# carte_ecureuil2026.net
KiCad netlist of a schematic drawn in Altium Designer
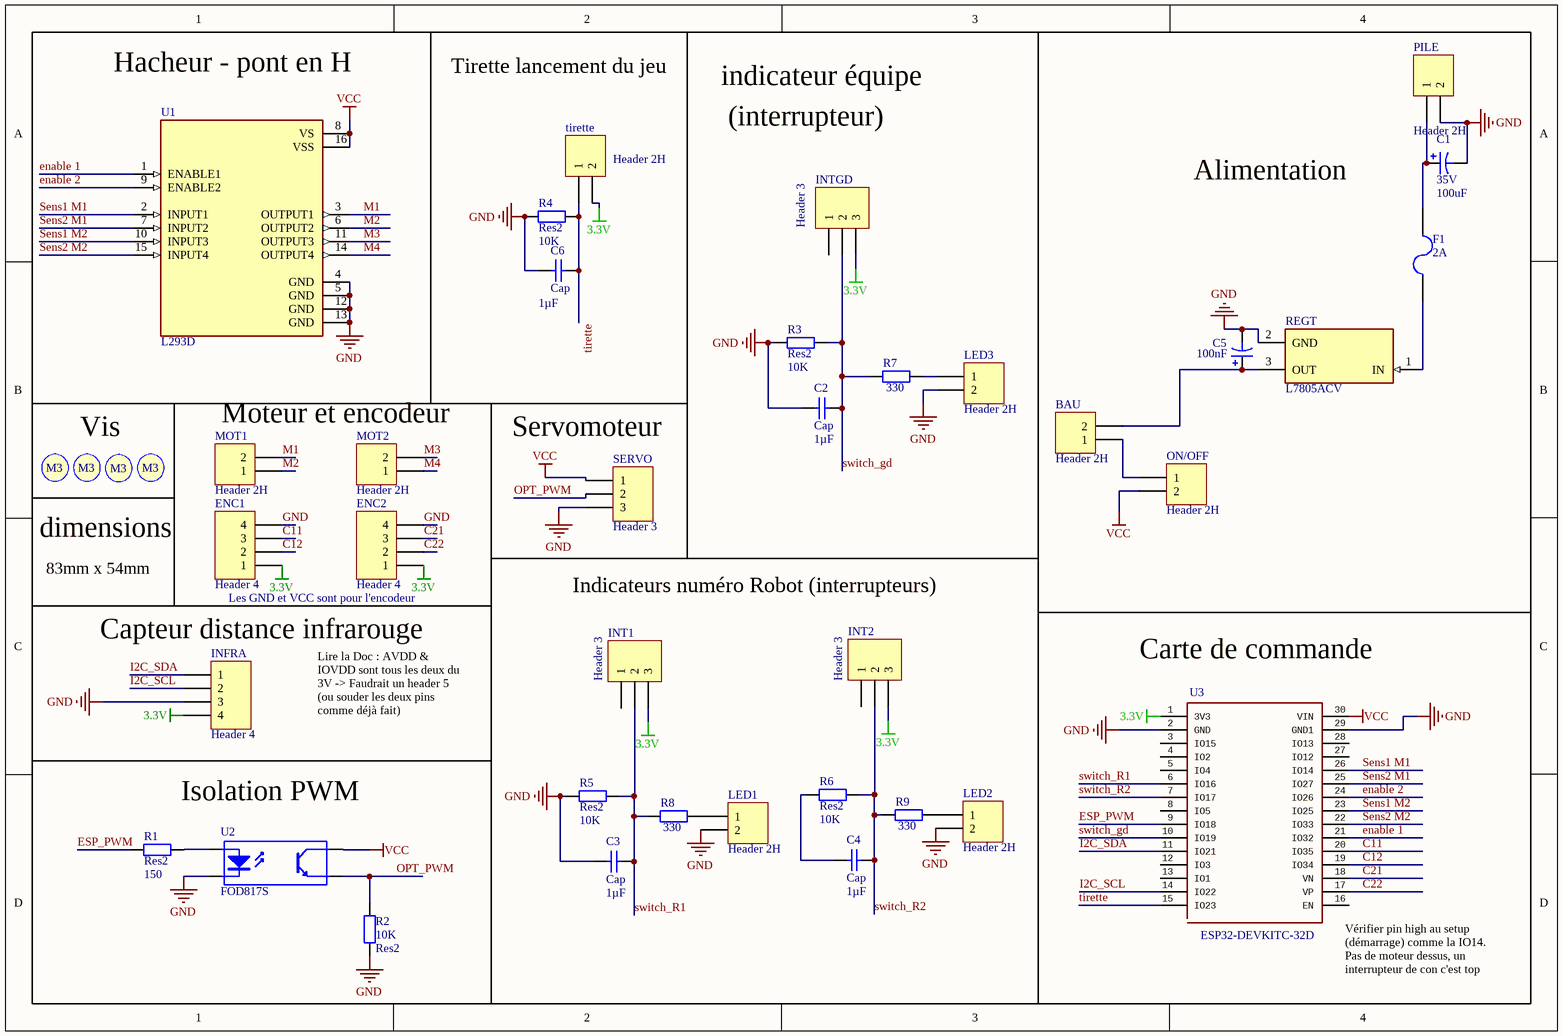
[diagram p0: carte_ecureuil2026.SchDoc]

(export (version "E")
  (design (tool "Eeschema 10.0.6"))
  (components
    (comp (ref "BAU")
      (value "Header 2H")
      (footprint "JST_B2B-XH-A_(LF)(SN)")
      (description "Header, 2-Pin, Right Angle")
      (fields (field (name "PUBLISHER") "Altium Limited"))
      (libsource (lib "") (part "Header 2H_2"))
    )
    (comp (ref "C1")
      (value "35V")
      (footprint "Condensateur")
      (description "Polarized Capacitor (Radial)")
      (fields (field (name "ALTIUM_VALUE") "100uF") (field (name "PUBLISHER") "Altium Limited"))
      (libsource (lib "Miscellaneous Devices") (part "Cap Pol1"))
    )
    (comp (ref "C2")
      (value "Cap")
      (footprint "Capacitor 1206")
      (description "Capacitor")
      (fields (field (name "ALTIUM_VALUE") "1µF") (field (name "PUBLISHER") "Altium Limited"))
      (libsource (lib "Miscellaneous Devices") (part "Cap"))
    )
    (comp (ref "C3")
      (value "Cap")
      (footprint "Capacitor 1206")
      (description "Capacitor")
      (fields (field (name "ALTIUM_VALUE") "1µF") (field (name "PUBLISHER") "Altium Limited"))
      (libsource (lib "Miscellaneous Devices") (part "Cap"))
    )
    (comp (ref "C4")
      (value "Cap")
      (footprint "Capacitor 1206")
      (description "Capacitor")
      (fields (field (name "ALTIUM_VALUE") "1µF") (field (name "PUBLISHER") "Altium Limited"))
      (libsource (lib "Miscellaneous Devices") (part "Cap"))
    )
    (comp (ref "C5")
      (value "100nF")
      (footprint "Condensateur")
      (description "Polarized Capacitor (Radial)")
      (fields (field (name "Comment") "35V") (field (name "PUBLISHER") "Altium Limited"))
      (libsource (lib "Miscellaneous Devices") (part "Cap Pol1"))
    )
    (comp (ref "C6")
      (value "Cap")
      (footprint "Capacitor 1206")
      (description "Capacitor")
      (fields (field (name "ALTIUM_VALUE") "1µF") (field (name "PUBLISHER") "Altium Limited"))
      (libsource (lib "Miscellaneous Devices") (part "Cap"))
    )
    (comp (ref "ENC1")
      (value "Header 4")
      (footprint "B4BXHALFSN")
      (description "Header, 4-Pin")
      (fields (field (name "PUBLISHER") "Altium Limited"))
      (libsource (lib "Miscellaneous Connectors") (part "Header 4"))
    )
    (comp (ref "ENC2")
      (value "Header 4")
      (footprint "B4BXHALFSN")
      (description "Header, 4-Pin")
      (fields (field (name "PUBLISHER") "Altium Limited"))
      (libsource (lib "Miscellaneous Connectors") (part "Header 4"))
    )
    (comp (ref "F1")
      (value "2A")
      (footprint "3.5X2.8X1.9")
      (description "Resettable Fuse αA / JF")
      (fields (field (name "PUBLISHER") "Altium Limited"))
      (libsource (lib "Miscellaneous Devices") (part "Fuse 2"))
    )
    (comp (ref "INFRA")
      (value "Header 4")
      (footprint "B4BXHALFSN")
      (description "Header, 4-Pin")
      (fields (field (name "PUBLISHER") "Altium Limited"))
      (libsource (lib "") (part "Header 4_1"))
    )
    (comp (ref "INT1")
      (value "Header 3")
      (footprint "JST_B3B-XH-A(LF)(SN)")
      (description "Header, 3-Pin")
      (fields (field (name "PUBLISHER") "Altium Limited"))
      (libsource (lib "Miscellaneous Connectors") (part "Header 3"))
    )
    (comp (ref "INT2")
      (value "Header 3")
      (footprint "JST_B3B-XH-A(LF)(SN)")
      (description "Header, 3-Pin")
      (fields (field (name "PUBLISHER") "Altium Limited"))
      (libsource (lib "Miscellaneous Connectors") (part "Header 3"))
    )
    (comp (ref "INTGD")
      (value "Header 3")
      (footprint "JST_B3B-XH-A(LF)(SN)")
      (description "Header, 3-Pin")
      (fields (field (name "PUBLISHER") "Altium Limited"))
      (libsource (lib "Miscellaneous Connectors") (part "Header 3"))
    )
    (comp (ref "LED1")
      (value "Header 2H")
      (footprint "JST_B2B-XH-A_(LF)(SN)")
      (description "Header, 2-Pin, Right Angle")
      (fields (field (name "PUBLISHER") "Altium Limited"))
      (libsource (lib "Miscellaneous Connectors") (part "Header 2H"))
    )
    (comp (ref "LED2")
      (value "Header 2H")
      (footprint "JST_B2B-XH-A_(LF)(SN)")
      (description "Header, 2-Pin, Right Angle")
      (fields (field (name "PUBLISHER") "Altium Limited"))
      (libsource (lib "Miscellaneous Connectors") (part "Header 2H"))
    )
    (comp (ref "LED3")
      (value "Header 2H")
      (footprint "JST_B2B-XH-A_(LF)(SN)")
      (description "Header, 2-Pin, Right Angle")
      (fields (field (name "PUBLISHER") "Altium Limited"))
      (libsource (lib "Miscellaneous Connectors") (part "Header 2H"))
    )
    (comp (ref "MOT1")
      (value "Header 2H")
      (footprint "JST_B2B-XH-A_(LF)(SN)")
      (description "Header, 2-Pin, Right Angle")
      (fields (field (name "PUBLISHER") "Altium Limited"))
      (libsource (lib "") (part "Header 2H_2"))
    )
    (comp (ref "MOT2")
      (value "Header 2H")
      (footprint "JST_B2B-XH-A_(LF)(SN)")
      (description "Header, 2-Pin, Right Angle")
      (fields (field (name "PUBLISHER") "Altium Limited"))
      (libsource (lib "") (part "Header 2H_2"))
    )
    (comp (ref "ON/OFF")
      (value "Header 2H")
      (footprint "JST_B2B-XH-A_(LF)(SN)")
      (description "Header, 2-Pin, Right Angle")
      (fields (field (name "PUBLISHER") "Altium Limited"))
      (libsource (lib "Miscellaneous Connectors") (part "Header 2H"))
    )
    (comp (ref "PILE")
      (value "Header 2H")
      (footprint "JST_B2B-XH-A_(LF)(SN)")
      (description "Header, 2-Pin, Right Angle")
      (fields (field (name "PUBLISHER") "Altium Limited"))
      (libsource (lib "") (part "Header 2H_1"))
    )
    (comp (ref "R1")
      (value "Res2")
      (footprint "Resistor 1206")
      (description "Resistor")
      (fields (field (name "ALTIUM_VALUE") "150") (field (name "PUBLISHER") "Altium Limited"))
      (libsource (lib "Miscellaneous Devices") (part "Res2"))
    )
    (comp (ref "R2")
      (value "Res2")
      (footprint "Resistor 1206")
      (description "Resistor")
      (fields (field (name "ALTIUM_VALUE") "10K") (field (name "PUBLISHER") "Altium Limited"))
      (libsource (lib "") (part "Res2_1"))
    )
    (comp (ref "R3")
      (value "Res2")
      (footprint "Resistor 1206")
      (description "Resistor")
      (fields (field (name "ALTIUM_VALUE") "10K") (field (name "PUBLISHER") "Altium Limited"))
      (libsource (lib "Miscellaneous Devices") (part "Res2"))
    )
    (comp (ref "R4")
      (value "Res2")
      (footprint "Resistor 1206")
      (description "Resistor")
      (fields (field (name "ALTIUM_VALUE") "10K") (field (name "PUBLISHER") "Altium Limited"))
      (libsource (lib "Miscellaneous Devices") (part "Res2"))
    )
    (comp (ref "R5")
      (value "Res2")
      (footprint "Resistor 1206")
      (description "Resistor")
      (fields (field (name "ALTIUM_VALUE") "10K") (field (name "PUBLISHER") "Altium Limited"))
      (libsource (lib "Miscellaneous Devices") (part "Res2"))
    )
    (comp (ref "R6")
      (value "Res2")
      (footprint "Resistor 1206")
      (description "Resistor")
      (fields (field (name "ALTIUM_VALUE") "10K") (field (name "PUBLISHER") "Altium Limited"))
      (libsource (lib "Miscellaneous Devices") (part "Res2"))
    )
    (comp (ref "R7")
      (value "330")
      (footprint "Resistor 1206")
      (description "Resistor")
      (fields (field (name "Comment") "Res2") (field (name "PUBLISHER") "Altium Limited"))
      (libsource (lib "Miscellaneous Devices") (part "Res2"))
    )
    (comp (ref "R8")
      (value "330")
      (footprint "Resistor 1206")
      (description "Resistor")
      (fields (field (name "Comment") "Res2") (field (name "PUBLISHER") "Altium Limited"))
      (libsource (lib "Miscellaneous Devices") (part "Res2"))
    )
    (comp (ref "R9")
      (value "330")
      (footprint "Resistor 1206")
      (description "Resistor")
      (fields (field (name "Comment") "Res2") (field (name "PUBLISHER") "Altium Limited"))
      (libsource (lib "Miscellaneous Devices") (part "Res2"))
    )
    (comp (ref "REGT")
      (value "L7805ACV")
      (footprint "TO254P460X1020X1945-3P")
      (description "Linear Voltage Regulator IC Positive Fixed 1 Output 1.5A TO-220")
      (fields (field (name "MF") "STMicroelectronics"))
      (libsource (lib "L7805ACV") (part "L7805ACV"))
    )
    (comp (ref "S1")
      (value "Screw M3")
      (footprint "Screw M3")
      (libsource (lib "Robot_2019") (part "Screw M3"))
    )
    (comp (ref "S2")
      (value "Screw M3")
      (footprint "Screw M3")
      (libsource (lib "Robot_2019") (part "Screw M3"))
    )
    (comp (ref "S3")
      (value "Screw M3")
      (footprint "Screw M3")
      (libsource (lib "Robot_2019") (part "Screw M3"))
    )
    (comp (ref "S4")
      (value "Screw M3")
      (footprint "Screw M3")
      (libsource (lib "Robot_2019") (part "Screw M3"))
    )
    (comp (ref "SERVO")
      (value "Header 3")
      (footprint "JST_B3B-XH-A(LF)(SN)")
      (description "Header, 3-Pin")
      (fields (field (name "PUBLISHER") "Altium Limited"))
      (libsource (lib "") (part "Header 3_1"))
    )
    (comp (ref "tirette")
      (value "Header 2H")
      (footprint "JST_B2B-XH-A_(LF)(SN)")
      (description "Header, 2-Pin, Right Angle")
      (fields (field (name "PUBLISHER") "Altium Limited"))
      (libsource (lib "") (part "Header 2H_1"))
    )
    (comp (ref "U1")
      (value "L293D")
      (footprint "DIP880W50P254L2000H510Q16")
      (description "Bipolar Motor Driver - Parallel 16-PowerDIP")
      (fields (field (name "MF") "STMicroelectronics"))
      (libsource (lib "L293D") (part "L293D"))
    )
    (comp (ref "U2")
      (value "FOD817S")
      (footprint "SOP254P1016X385-4N")
      (description "4-Pin Phototransistor Optocoupler")
      (fields (field (name "PUBLISHER") "Altium Limited"))
      (libsource (lib "Miscellaneous Devices") (part "Optoisolator1"))
    )
    (comp (ref "U3")
      (value "ESP32-DEVKITC-32D")
      (footprint "MODULE_ESP32-DEVKITV1")
      (description "Eval Board For Esp-Wroom-32")
      (fields (field (name "MF") "Espressif Systems"))
      (libsource (lib "AltiumLibraryDDT") (part "ESP32-DEVKITC-32D"))
    )
  )
  (nets
    (net (code "1") (name "/C11") (class "Default")
      (node (ref "ENC1") (pin "3") (pinfunction "3_3") (pintype "passive"))
      (node (ref "U3") (pin "20") (pinfunction "IO35_20") (pintype "passive"))
    )
    (net (code "2") (name "/C12") (class "Default")
      (node (ref "ENC1") (pin "2") (pinfunction "2_2") (pintype "passive"))
      (node (ref "U3") (pin "19") (pinfunction "IO34_19") (pintype "passive"))
    )
    (net (code "3") (name "/C21") (class "Default")
      (node (ref "ENC2") (pin "3") (pinfunction "3_3") (pintype "passive"))
      (node (ref "U3") (pin "18") (pinfunction "VN_18") (pintype "passive"))
    )
    (net (code "4") (name "/C22") (class "Default")
      (node (ref "ENC2") (pin "2") (pinfunction "2_2") (pintype "passive"))
      (node (ref "U3") (pin "17") (pinfunction "VP_17") (pintype "passive"))
    )
    (net (code "5") (name "/ESP_PWM") (class "Default")
      (node (ref "R1") (pin "1") (pinfunction "1_1") (pintype "passive"))
      (node (ref "U3") (pin "9") (pinfunction "IO18_9") (pintype "passive"))
    )
    (net (code "6") (name "/I2C_SCL") (class "Default")
      (node (ref "INFRA") (pin "2") (pinfunction "2_2") (pintype "passive"))
      (node (ref "U3") (pin "14") (pinfunction "IO22_14") (pintype "passive"))
    )
    (net (code "7") (name "/I2C_SDA") (class "Default")
      (node (ref "INFRA") (pin "1") (pinfunction "1_1") (pintype "passive"))
      (node (ref "U3") (pin "11") (pinfunction "IO21_11") (pintype "passive"))
    )
    (net (code "8") (name "/M1") (class "Default")
      (node (ref "MOT1") (pin "2") (pinfunction "2_2") (pintype "passive"))
      (node (ref "U1") (pin "3") (pinfunction "OUTPUT1_3") (pintype "output"))
    )
    (net (code "9") (name "/M2") (class "Default")
      (node (ref "MOT1") (pin "1") (pinfunction "1_1") (pintype "passive"))
      (node (ref "U1") (pin "6") (pinfunction "OUTPUT2_6") (pintype "output"))
    )
    (net (code "10") (name "/M3") (class "Default")
      (node (ref "MOT2") (pin "2") (pinfunction "2_2") (pintype "passive"))
      (node (ref "U1") (pin "11") (pinfunction "OUTPUT3_11") (pintype "output"))
    )
    (net (code "11") (name "/M4") (class "Default")
      (node (ref "MOT2") (pin "1") (pinfunction "1_1") (pintype "passive"))
      (node (ref "U1") (pin "14") (pinfunction "OUTPUT4_14") (pintype "output"))
    )
    (net (code "12") (name "/OPT_PWM") (class "Default")
      (node (ref "R2") (pin "2") (pinfunction "2_2") (pintype "passive"))
      (node (ref "SERVO") (pin "2") (pinfunction "2_2") (pintype "passive"))
      (node (ref "U2") (pin "3") (pinfunction "E_3") (pintype "passive"))
    )
    (net (code "13") (name "/Sens1 M1") (class "Default")
      (node (ref "U1") (pin "2") (pinfunction "INPUT1_2") (pintype "input"))
      (node (ref "U3") (pin "26") (pinfunction "IO14_26") (pintype "passive"))
    )
    (net (code "14") (name "/Sens1 M2") (class "Default")
      (node (ref "U1") (pin "10") (pinfunction "INPUT3_10") (pintype "input"))
      (node (ref "U3") (pin "23") (pinfunction "IO25_23") (pintype "passive"))
    )
    (net (code "15") (name "/Sens2 M1") (class "Default")
      (node (ref "U1") (pin "7") (pinfunction "INPUT2_7") (pintype "input"))
      (node (ref "U3") (pin "25") (pinfunction "IO27_25") (pintype "passive"))
    )
    (net (code "16") (name "/Sens2 M2") (class "Default")
      (node (ref "U1") (pin "15") (pinfunction "INPUT4_15") (pintype "input"))
      (node (ref "U3") (pin "22") (pinfunction "IO33_22") (pintype "passive"))
    )
    (net (code "17") (name "/enable 1") (class "Default")
      (node (ref "U1") (pin "1") (pinfunction "ENABLE1_1") (pintype "input"))
      (node (ref "U3") (pin "21") (pinfunction "IO32_21") (pintype "passive"))
    )
    (net (code "18") (name "/enable 2") (class "Default")
      (node (ref "U1") (pin "9") (pinfunction "ENABLE2_9") (pintype "input"))
      (node (ref "U3") (pin "24") (pinfunction "IO26_24") (pintype "passive"))
    )
    (net (code "19") (name "/switch_R1") (class "Default")
      (node (ref "C3") (pin "2") (pinfunction "2_2") (pintype "passive"))
      (node (ref "INT1") (pin "2") (pinfunction "2_2") (pintype "passive"))
      (node (ref "R5") (pin "2") (pinfunction "2_2") (pintype "passive"))
      (node (ref "R8") (pin "1") (pinfunction "1_1") (pintype "passive"))
      (node (ref "U3") (pin "6") (pinfunction "IO16_6") (pintype "passive"))
    )
    (net (code "20") (name "/switch_R2") (class "Default")
      (node (ref "C4") (pin "2") (pinfunction "2_2") (pintype "passive"))
      (node (ref "INT2") (pin "2") (pinfunction "2_2") (pintype "passive"))
      (node (ref "R6") (pin "2") (pinfunction "2_2") (pintype "passive"))
      (node (ref "R9") (pin "1") (pinfunction "1_1") (pintype "passive"))
      (node (ref "U3") (pin "7") (pinfunction "IO17_7") (pintype "passive"))
    )
    (net (code "21") (name "/switch_gd") (class "Default")
      (node (ref "C2") (pin "2") (pinfunction "2_2") (pintype "passive"))
      (node (ref "INTGD") (pin "2") (pinfunction "2_2") (pintype "passive"))
      (node (ref "R3") (pin "2") (pinfunction "2_2") (pintype "passive"))
      (node (ref "R7") (pin "1") (pinfunction "1_1") (pintype "passive"))
      (node (ref "U3") (pin "10") (pinfunction "IO19_10") (pintype "passive"))
    )
    (net (code "22") (name "/tirette") (class "Default")
      (node (ref "C6") (pin "2") (pinfunction "2_2") (pintype "passive"))
      (node (ref "R4") (pin "2") (pinfunction "2_2") (pintype "passive"))
      (node (ref "U3") (pin "15") (pinfunction "IO23_15") (pintype "passive"))
      (node (ref "tirette") (pin "1") (pinfunction "1_1") (pintype "passive"))
    )
    (net (code "23") (name "3.3V") (class "Default")
      (node (ref "ENC1") (pin "1") (pinfunction "1_1") (pintype "passive"))
      (node (ref "ENC2") (pin "1") (pinfunction "1_1") (pintype "passive"))
      (node (ref "INFRA") (pin "4") (pinfunction "4_4") (pintype "passive"))
      (node (ref "INT1") (pin "3") (pinfunction "3_3") (pintype "passive"))
      (node (ref "INT2") (pin "3") (pinfunction "3_3") (pintype "passive"))
      (node (ref "INTGD") (pin "3") (pinfunction "3_3") (pintype "passive"))
      (node (ref "U3") (pin "1") (pinfunction "3V3_1") (pintype "passive"))
      (node (ref "tirette") (pin "2") (pinfunction "2_2") (pintype "passive"))
    )
    (net (code "24") (name "GND") (class "Default")
      (node (ref "C1") (pin "2") (pinfunction "2_2") (pintype "passive"))
      (node (ref "C2") (pin "1") (pinfunction "1_1") (pintype "passive"))
      (node (ref "C3") (pin "1") (pinfunction "1_1") (pintype "passive"))
      (node (ref "C5") (pin "2") (pinfunction "2_2") (pintype "passive"))
      (node (ref "C6") (pin "1") (pinfunction "1_1") (pintype "passive"))
      (node (ref "ENC1") (pin "4") (pinfunction "4_4") (pintype "passive"))
      (node (ref "ENC2") (pin "4") (pinfunction "4_4") (pintype "passive"))
      (node (ref "INFRA") (pin "3") (pinfunction "3_3") (pintype "passive"))
      (node (ref "LED1") (pin "2") (pinfunction "2_2") (pintype "passive"))
      (node (ref "LED2") (pin "2") (pinfunction "2_2") (pintype "passive"))
      (node (ref "LED3") (pin "2") (pinfunction "2_2") (pintype "passive"))
      (node (ref "PILE") (pin "2") (pinfunction "2_2") (pintype "passive"))
      (node (ref "R2") (pin "1") (pinfunction "1_1") (pintype "passive"))
      (node (ref "R3") (pin "1") (pinfunction "1_1") (pintype "passive"))
      (node (ref "R4") (pin "1") (pinfunction "1_1") (pintype "passive"))
      (node (ref "R5") (pin "1") (pinfunction "1_1") (pintype "passive"))
      (node (ref "REGT") (pin "2") (pinfunction "GND_2") (pintype "power_in"))
      (node (ref "SERVO") (pin "3") (pinfunction "3_3") (pintype "passive"))
      (node (ref "U1") (pin "12") (pinfunction "GND_12") (pintype "power_in"))
      (node (ref "U1") (pin "13") (pinfunction "GND_13") (pintype "power_in"))
      (node (ref "U1") (pin "4") (pinfunction "GND_4") (pintype "power_in"))
      (node (ref "U1") (pin "5") (pinfunction "GND_5") (pintype "power_in"))
      (node (ref "U2") (pin "2") (pinfunction "K_2") (pintype "passive"))
      (node (ref "U3") (pin "2") (pinfunction "GND_2") (pintype "passive"))
      (node (ref "U3") (pin "29") (pinfunction "GND1_29") (pintype "passive"))
    )
    (net (code "25") (name "Net-(BAU-Pad1)") (class "Default")
      (node (ref "BAU") (pin "1") (pinfunction "1_1") (pintype "passive"))
      (node (ref "ON/OFF") (pin "1") (pinfunction "1_1") (pintype "passive"))
    )
    (net (code "26") (name "Net-(C1-Pad1)") (class "Default")
      (node (ref "C1") (pin "1") (pinfunction "1_1") (pintype "passive"))
      (node (ref "F1") (pin "2") (pinfunction "2_2") (pintype "passive"))
      (node (ref "PILE") (pin "1") (pinfunction "1_1") (pintype "passive"))
    )
    (net (code "27") (name "Net-(C4-Pad1)") (class "Default")
      (node (ref "C4") (pin "1") (pinfunction "1_1") (pintype "passive"))
      (node (ref "R6") (pin "1") (pinfunction "1_1") (pintype "passive"))
    )
    (net (code "28") (name "Net-(LED1-Pad1)") (class "Default")
      (node (ref "LED1") (pin "1") (pinfunction "1_1") (pintype "passive"))
      (node (ref "R8") (pin "2") (pinfunction "2_2") (pintype "passive"))
    )
    (net (code "29") (name "Net-(LED2-Pad1)") (class "Default")
      (node (ref "LED2") (pin "1") (pinfunction "1_1") (pintype "passive"))
      (node (ref "R9") (pin "2") (pinfunction "2_2") (pintype "passive"))
    )
    (net (code "30") (name "Net-(LED3-Pad1)") (class "Default")
      (node (ref "LED3") (pin "1") (pinfunction "1_1") (pintype "passive"))
      (node (ref "R7") (pin "2") (pinfunction "2_2") (pintype "passive"))
    )
    (net (code "31") (name "Net-(REGT-IN)") (class "Default")
      (node (ref "F1") (pin "1") (pinfunction "1_1") (pintype "passive"))
      (node (ref "REGT") (pin "1") (pinfunction "IN_1") (pintype "input"))
    )
    (net (code "32") (name "Net-(REGT-OUT)") (class "Default")
      (node (ref "BAU") (pin "2") (pinfunction "2_2") (pintype "passive"))
      (node (ref "C5") (pin "1") (pinfunction "1_1") (pintype "passive"))
      (node (ref "REGT") (pin "3") (pinfunction "OUT_3") (pintype "power_in"))
    )
    (net (code "33") (name "Net-(U2-A)") (class "Default")
      (node (ref "R1") (pin "2") (pinfunction "2_2") (pintype "passive"))
      (node (ref "U2") (pin "1") (pinfunction "A_1") (pintype "passive"))
    )
    (net (code "34") (name "VCC") (class "Default")
      (node (ref "ON/OFF") (pin "2") (pinfunction "2_2") (pintype "passive"))
      (node (ref "SERVO") (pin "1") (pinfunction "1_1") (pintype "passive"))
      (node (ref "U1") (pin "16") (pinfunction "VSS_16") (pintype "power_in"))
      (node (ref "U1") (pin "8") (pinfunction "VS_8") (pintype "power_in"))
      (node (ref "U2") (pin "4") (pinfunction "C_4") (pintype "passive"))
      (node (ref "U3") (pin "30") (pinfunction "VIN_30") (pintype "passive"))
    )
    (net (code "35") (name "unconnected-(INT1-Pad1)") (class "Default")
      (node (ref "INT1") (pin "1") (pinfunction "1_1") (pintype "passive"))
    )
    (net (code "36") (name "unconnected-(INT2-Pad1)") (class "Default")
      (node (ref "INT2") (pin "1") (pinfunction "1_1") (pintype "passive"))
    )
    (net (code "37") (name "unconnected-(INTGD-Pad1)") (class "Default")
      (node (ref "INTGD") (pin "1") (pinfunction "1_1") (pintype "passive"))
    )
    (net (code "38") (name "unconnected-(U3-EN-Pad16)") (class "Default")
      (node (ref "U3") (pin "16") (pinfunction "EN_16") (pintype "passive"))
    )
    (net (code "39") (name "unconnected-(U3-IO1-Pad13)") (class "Default")
      (node (ref "U3") (pin "13") (pinfunction "IO1_13") (pintype "passive"))
    )
    (net (code "40") (name "unconnected-(U3-IO2-Pad4)") (class "Default")
      (node (ref "U3") (pin "4") (pinfunction "IO2_4") (pintype "passive"))
    )
    (net (code "41") (name "unconnected-(U3-IO3-Pad12)") (class "Default")
      (node (ref "U3") (pin "12") (pinfunction "IO3_12") (pintype "passive"))
    )
    (net (code "42") (name "unconnected-(U3-IO4-Pad5)") (class "Default")
      (node (ref "U3") (pin "5") (pinfunction "IO4_5") (pintype "passive"))
    )
    (net (code "43") (name "unconnected-(U3-IO5-Pad8)") (class "Default")
      (node (ref "U3") (pin "8") (pinfunction "IO5_8") (pintype "passive"))
    )
    (net (code "44") (name "unconnected-(U3-IO12-Pad27)") (class "Default")
      (node (ref "U3") (pin "27") (pinfunction "IO12_27") (pintype "passive"))
    )
    (net (code "45") (name "unconnected-(U3-IO13-Pad28)") (class "Default")
      (node (ref "U3") (pin "28") (pinfunction "IO13_28") (pintype "passive"))
    )
    (net (code "46") (name "unconnected-(U3-IO15-Pad3)") (class "Default")
      (node (ref "U3") (pin "3") (pinfunction "IO15_3") (pintype "passive"))
    )
  )
)
